# Sheet3_MCU.net
KiCad netlist of a schematic drawn in Altium Designer
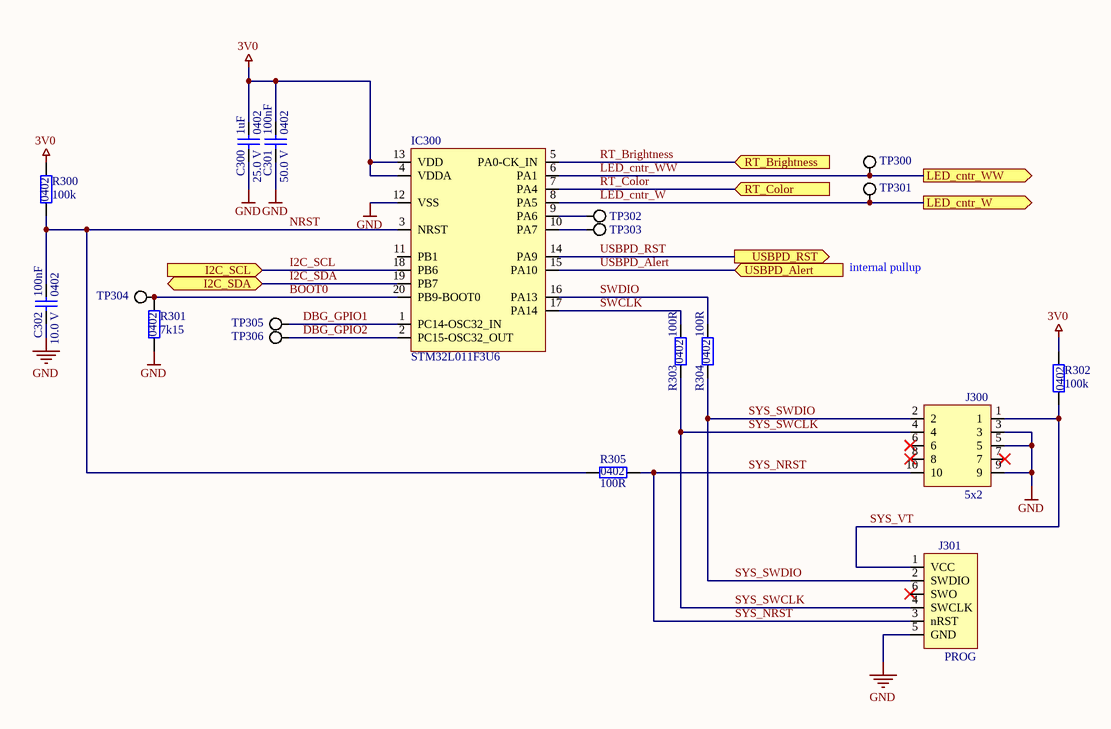
[diagram p0: Sheet3_MCU.SchDoc]

(export (version "E")
  (design (tool "Eeschema 10.0.6"))
  (components
    (comp (ref "C300")
      (value "C 1uF 0402 25V")
      (footprint "0402")
      (description "CAP CER 1UF 25V X5R 0402")
      (fields
        (field (name "MANUFACTURER") "Taiyo Yuden")
        (field (name "MANUFACTURER PART NUMBER") "TMK105BJ105MV-F")
        (field (name "CAPACITANCE") "1uF")
        (field (name "VOLTAGE") "25.0 V")
      )
      (libsource (lib "CS_Part_Library") (part "CAP_1uF_25V_0402"))
    )
    (comp (ref "C301")
      (value "C 100nF 0402 50V")
      (footprint "0402")
      (description "CAP CER 0.1UF 50V X7R 0402")
      (fields
        (field (name "MANUFACTURER") "Murata Electronics")
        (field (name "MANUFACTURER PART NUMBER") "GRM155R71H104KE14J")
        (field (name "CAPACITANCE") "100nF")
        (field (name "VOLTAGE") "50.0 V")
      )
      (libsource (lib "CS_Part_Library") (part "CAP_100nF_50V_0402"))
    )
    (comp (ref "C302")
      (value "C 100nF 0402 10V")
      (footprint "0402")
      (description "CAP CER 0.1UF 10V X5R 0402")
      (fields
        (field (name "MANUFACTURER") "Samsung Electro-Mechanics")
        (field (name "MANUFACTURER PART NUMBER") "CL05A104MP5NNNC")
        (field (name "CAPACITANCE") "100nF")
        (field (name "VOLTAGE") "10.0 V")
      )
      (libsource (lib "CS_Part_Library") (part "CAP_100nF_10V_0402"))
    )
    (comp (ref "IC300")
      (value "STM32L011F3U6")
      (footprint "UFQFN-20")
      (description "IC MCU 32BIT 8KB FLASH 20UFQFPN")
      (fields
        (field (name "MANUFACTURER") "STMicroelectronics")
        (field (name "MANUFACTURER PART NUMBER") "STM32L011F3U6TR")
      )
      (libsource (lib "CS_Part_Library") (part "IC_MCU_STM32L011F3U6"))
    )
    (comp (ref "J300")
      (value "5x2")
      (footprint "J_MH5x2_1.27-STM32")
      (description "CONN HEADER SMD 10POS 1.27MM")
      (fields
        (field (name "MANUFACTURER") "Sullins Connector Solutions")
        (field (name "MANUFACTURER PART NUMBER") "GRPB052VWQS-RC")
      )
      (libsource (lib "Symbols") (part "J_MH5x2_1.27"))
    )
    (comp (ref "J301")
      (value "PROG")
      (footprint "J_TC2030-IDC-NL")
      (description "SWD Programmer No Legs")
      (fields (field (name "MANUFACTURER") "Tag_connect") (field (name "MANUFACTURER PART NUMBER") "TC2030"))
      (libsource (lib "CS_Part_Library") (part "J_TC2030-IDC-NL"))
    )
    (comp (ref "R300")
      (value "R 100k 0402")
      (footprint "0402")
      (description "RES 100K OHM 5% 1/16W 0402")
      (fields
        (field (name "MANUFACTURER") "YAGEO")
        (field (name "MANUFACTURER PART NUMBER") "RC0402JR-07100KL")
        (field (name "RESISTANCE") "100k")
      )
      (libsource (lib "") (part "R_100k_0402_1"))
    )
    (comp (ref "R301")
      (value "R 7k15 0402")
      (footprint "0402")
      (description "RES 7.15K OHM 1% 1/16W 0402")
      (fields
        (field (name "MANUFACTURER") "Stackpole Electronics Inc")
        (field (name "MANUFACTURER PART NUMBER") "RMCF0402FT7K15")
        (field (name "RESISTANCE") "7k15")
      )
      (libsource (lib "CS_Part_Library") (part "R_7k15_0402"))
    )
    (comp (ref "R302")
      (value "R 100k 0402")
      (footprint "0402")
      (description "RES 100K OHM 5% 1/16W 0402")
      (fields
        (field (name "MANUFACTURER") "YAGEO")
        (field (name "MANUFACTURER PART NUMBER") "RC0402JR-07100KL")
        (field (name "RESISTANCE") "100k")
      )
      (libsource (lib "CS_Part_Library") (part "R_100k_0402"))
    )
    (comp (ref "R303")
      (value "R 100R 0402")
      (footprint "0402")
      (description "RES 100 OHM 1% 1/16W 0402")
      (fields
        (field (name "MANUFACTURER") "Stackpole Electronics Inc")
        (field (name "MANUFACTURER PART NUMBER") "RMCF0402FT100R")
        (field (name "RESISTANCE") "100R")
      )
      (libsource (lib "CS_Part_Library") (part "R_100R_0402"))
    )
    (comp (ref "R304")
      (value "R 100R 0402")
      (footprint "0402")
      (description "RES 100 OHM 1% 1/16W 0402")
      (fields
        (field (name "MANUFACTURER") "Stackpole Electronics Inc")
        (field (name "MANUFACTURER PART NUMBER") "RMCF0402FT100R")
        (field (name "RESISTANCE") "100R")
      )
      (libsource (lib "CS_Part_Library") (part "R_100R_0402"))
    )
    (comp (ref "R305")
      (value "R 100R 0402")
      (footprint "0402")
      (description "RES 100 OHM 1% 1/16W 0402")
      (fields
        (field (name "MANUFACTURER") "Stackpole Electronics Inc")
        (field (name "MANUFACTURER PART NUMBER") "RMCF0402FT100R")
        (field (name "RESISTANCE") "100R")
      )
      (libsource (lib "") (part "R_100R_0402_1"))
    )
    (comp (ref "TP300")
      (value "TP")
      (footprint "TP_1mm")
      (description "Test Point 1mm")
      (libsource (lib "CS_Part_Library") (part "TP_1mm"))
    )
    (comp (ref "TP301")
      (value "TP")
      (footprint "TP_1mm")
      (description "Test Point 1mm")
      (libsource (lib "CS_Part_Library") (part "TP_1mm"))
    )
    (comp (ref "TP302")
      (value "TP")
      (footprint "TP_1mm")
      (description "Test Point 1mm")
      (libsource (lib "CS_Part_Library") (part "TP_1mm"))
    )
    (comp (ref "TP303")
      (value "TP")
      (footprint "TP_1mm")
      (description "Test Point 1mm")
      (libsource (lib "CS_Part_Library") (part "TP_1mm"))
    )
    (comp (ref "TP304")
      (value "TP")
      (footprint "TP_1mm")
      (description "Test Point 1mm")
      (libsource (lib "CS_Part_Library") (part "TP_1mm"))
    )
    (comp (ref "TP305")
      (value "TP")
      (footprint "TP_1mm")
      (description "Test Point 1mm")
      (libsource (lib "CS_Part_Library") (part "TP_1mm"))
    )
    (comp (ref "TP306")
      (value "TP")
      (footprint "TP_1mm")
      (description "Test Point 1mm")
      (libsource (lib "CS_Part_Library") (part "TP_1mm"))
    )
  )
  (nets
    (net (code "1") (name "/BOOT0") (class "Default")
      (node (ref "IC300") (pin "20") (pinfunction "PB9-BOOT0_20") (pintype "passive"))
      (node (ref "R301") (pin "2") (pinfunction "2_2") (pintype "passive"))
      (node (ref "TP304") (pin "1") (pinfunction "TP_1") (pintype "passive"))
    )
    (net (code "2") (name "/DBG_GPIO1") (class "Default")
      (node (ref "IC300") (pin "1") (pinfunction "PC14-OSC32_IN_1") (pintype "passive"))
      (node (ref "TP305") (pin "1") (pinfunction "TP_1") (pintype "passive"))
    )
    (net (code "3") (name "/DBG_GPIO2") (class "Default")
      (node (ref "IC300") (pin "2") (pinfunction "PC15-OSC32_OUT_2") (pintype "passive"))
      (node (ref "TP306") (pin "1") (pinfunction "TP_1") (pintype "passive"))
    )
    (net (code "4") (name "/I2C_SCL") (class "Default")
      (node (ref "IC300") (pin "18") (pinfunction "PB6_18") (pintype "passive"))
    )
    (net (code "5") (name "/I2C_SDA") (class "Default")
      (node (ref "IC300") (pin "19") (pinfunction "PB7_19") (pintype "passive"))
    )
    (net (code "6") (name "/LED_cntr_W") (class "Default")
      (node (ref "IC300") (pin "8") (pinfunction "PA5_8") (pintype "passive"))
      (node (ref "TP301") (pin "1") (pinfunction "TP_1") (pintype "passive"))
    )
    (net (code "7") (name "/LED_cntr_WW") (class "Default")
      (node (ref "IC300") (pin "6") (pinfunction "PA1_6") (pintype "passive"))
      (node (ref "TP300") (pin "1") (pinfunction "TP_1") (pintype "passive"))
    )
    (net (code "8") (name "/NRST") (class "Default")
      (node (ref "C302") (pin "2") (pinfunction "2_2") (pintype "passive"))
      (node (ref "IC300") (pin "3") (pinfunction "NRST_3") (pintype "passive"))
      (node (ref "R300") (pin "1") (pinfunction "1_1") (pintype "passive"))
      (node (ref "R305") (pin "1") (pinfunction "1_1") (pintype "passive"))
    )
    (net (code "9") (name "/RT_Brightness") (class "Default")
      (node (ref "IC300") (pin "5") (pinfunction "PA0-CK_IN_5") (pintype "passive"))
    )
    (net (code "10") (name "/RT_Color") (class "Default")
      (node (ref "IC300") (pin "7") (pinfunction "PA4_7") (pintype "passive"))
    )
    (net (code "11") (name "/SWCLK") (class "Default")
      (node (ref "IC300") (pin "17") (pinfunction "PA14_17") (pintype "passive"))
      (node (ref "R303") (pin "2") (pinfunction "2_2") (pintype "passive"))
    )
    (net (code "12") (name "/SWDIO") (class "Default")
      (node (ref "IC300") (pin "16") (pinfunction "PA13_16") (pintype "passive"))
      (node (ref "R304") (pin "2") (pinfunction "2_2") (pintype "passive"))
    )
    (net (code "13") (name "/SYS_NRST") (class "Default")
      (node (ref "J300") (pin "10") (pinfunction "10_10") (pintype "passive"))
      (node (ref "J301") (pin "3") (pinfunction "nRST_3") (pintype "passive"))
      (node (ref "R305") (pin "2") (pinfunction "2_2") (pintype "passive"))
    )
    (net (code "14") (name "/SYS_SWCLK") (class "Default")
      (node (ref "J300") (pin "4") (pinfunction "4_4") (pintype "passive"))
      (node (ref "J301") (pin "4") (pinfunction "SWCLK_4") (pintype "passive"))
      (node (ref "R303") (pin "1") (pinfunction "1_1") (pintype "passive"))
    )
    (net (code "15") (name "/SYS_SWDIO") (class "Default")
      (node (ref "J300") (pin "2") (pinfunction "2_2") (pintype "passive"))
      (node (ref "J301") (pin "2") (pinfunction "SWDIO_2") (pintype "passive"))
      (node (ref "R304") (pin "1") (pinfunction "1_1") (pintype "passive"))
    )
    (net (code "16") (name "/SYS_VT") (class "Default")
      (node (ref "J300") (pin "1") (pinfunction "1_1") (pintype "passive"))
      (node (ref "J301") (pin "1") (pinfunction "VCC_1") (pintype "passive"))
      (node (ref "R302") (pin "2") (pinfunction "2_2") (pintype "passive"))
    )
    (net (code "17") (name "/USBPD_Alert") (class "Default")
      (node (ref "IC300") (pin "15") (pinfunction "PA10_15") (pintype "passive"))
    )
    (net (code "18") (name "/USBPD_RST") (class "Default")
      (node (ref "IC300") (pin "14") (pinfunction "PA9_14") (pintype "passive"))
    )
    (net (code "19") (name "3V0") (class "Default")
      (node (ref "C300") (pin "2") (pinfunction "2_2") (pintype "passive"))
      (node (ref "C301") (pin "2") (pinfunction "2_2") (pintype "passive"))
      (node (ref "IC300") (pin "13") (pinfunction "VDD_13") (pintype "passive"))
      (node (ref "IC300") (pin "4") (pinfunction "VDDA_4") (pintype "passive"))
      (node (ref "R300") (pin "2") (pinfunction "2_2") (pintype "passive"))
      (node (ref "R302") (pin "1") (pinfunction "1_1") (pintype "passive"))
    )
    (net (code "20") (name "GND") (class "Default")
      (node (ref "C300") (pin "1") (pinfunction "1_1") (pintype "passive"))
      (node (ref "C301") (pin "1") (pinfunction "1_1") (pintype "passive"))
      (node (ref "C302") (pin "1") (pinfunction "1_1") (pintype "passive"))
      (node (ref "IC300") (pin "12") (pinfunction "VSS_12") (pintype "passive"))
      (node (ref "J300") (pin "3") (pinfunction "3_3") (pintype "passive"))
      (node (ref "J300") (pin "5") (pinfunction "5_5") (pintype "passive"))
      (node (ref "J300") (pin "9") (pinfunction "9_9") (pintype "passive"))
      (node (ref "J301") (pin "5") (pinfunction "GND_5") (pintype "passive"))
      (node (ref "R301") (pin "1") (pinfunction "1_1") (pintype "passive"))
    )
    (net (code "21") (name "Net-(IC300-PA6)") (class "Default")
      (node (ref "IC300") (pin "9") (pinfunction "PA6_9") (pintype "passive"))
      (node (ref "TP302") (pin "1") (pinfunction "TP_1") (pintype "passive"))
    )
    (net (code "22") (name "Net-(IC300-PA7)") (class "Default")
      (node (ref "IC300") (pin "10") (pinfunction "PA7_10") (pintype "passive"))
      (node (ref "TP303") (pin "1") (pinfunction "TP_1") (pintype "passive"))
    )
    (net (code "23") (name "unconnected-(IC300-PB1-Pad11)") (class "Default")
      (node (ref "IC300") (pin "11") (pinfunction "PB1_11") (pintype "passive"))
    )
    (net (code "24") (name "unconnected-(J300-Pad6)") (class "Default")
      (node (ref "J300") (pin "6") (pinfunction "6_6") (pintype "passive+no_connect"))
    )
    (net (code "25") (name "unconnected-(J300-Pad7)") (class "Default")
      (node (ref "J300") (pin "7") (pinfunction "7_7") (pintype "passive+no_connect"))
    )
    (net (code "26") (name "unconnected-(J300-Pad8)") (class "Default")
      (node (ref "J300") (pin "8") (pinfunction "8_8") (pintype "passive+no_connect"))
    )
    (net (code "27") (name "unconnected-(J301-SWO-Pad6)") (class "Default")
      (node (ref "J301") (pin "6") (pinfunction "SWO_6") (pintype "passive+no_connect"))
    )
  )
)
